# shifter.net
KiCad netlist of a schematic drawn in EAGLE
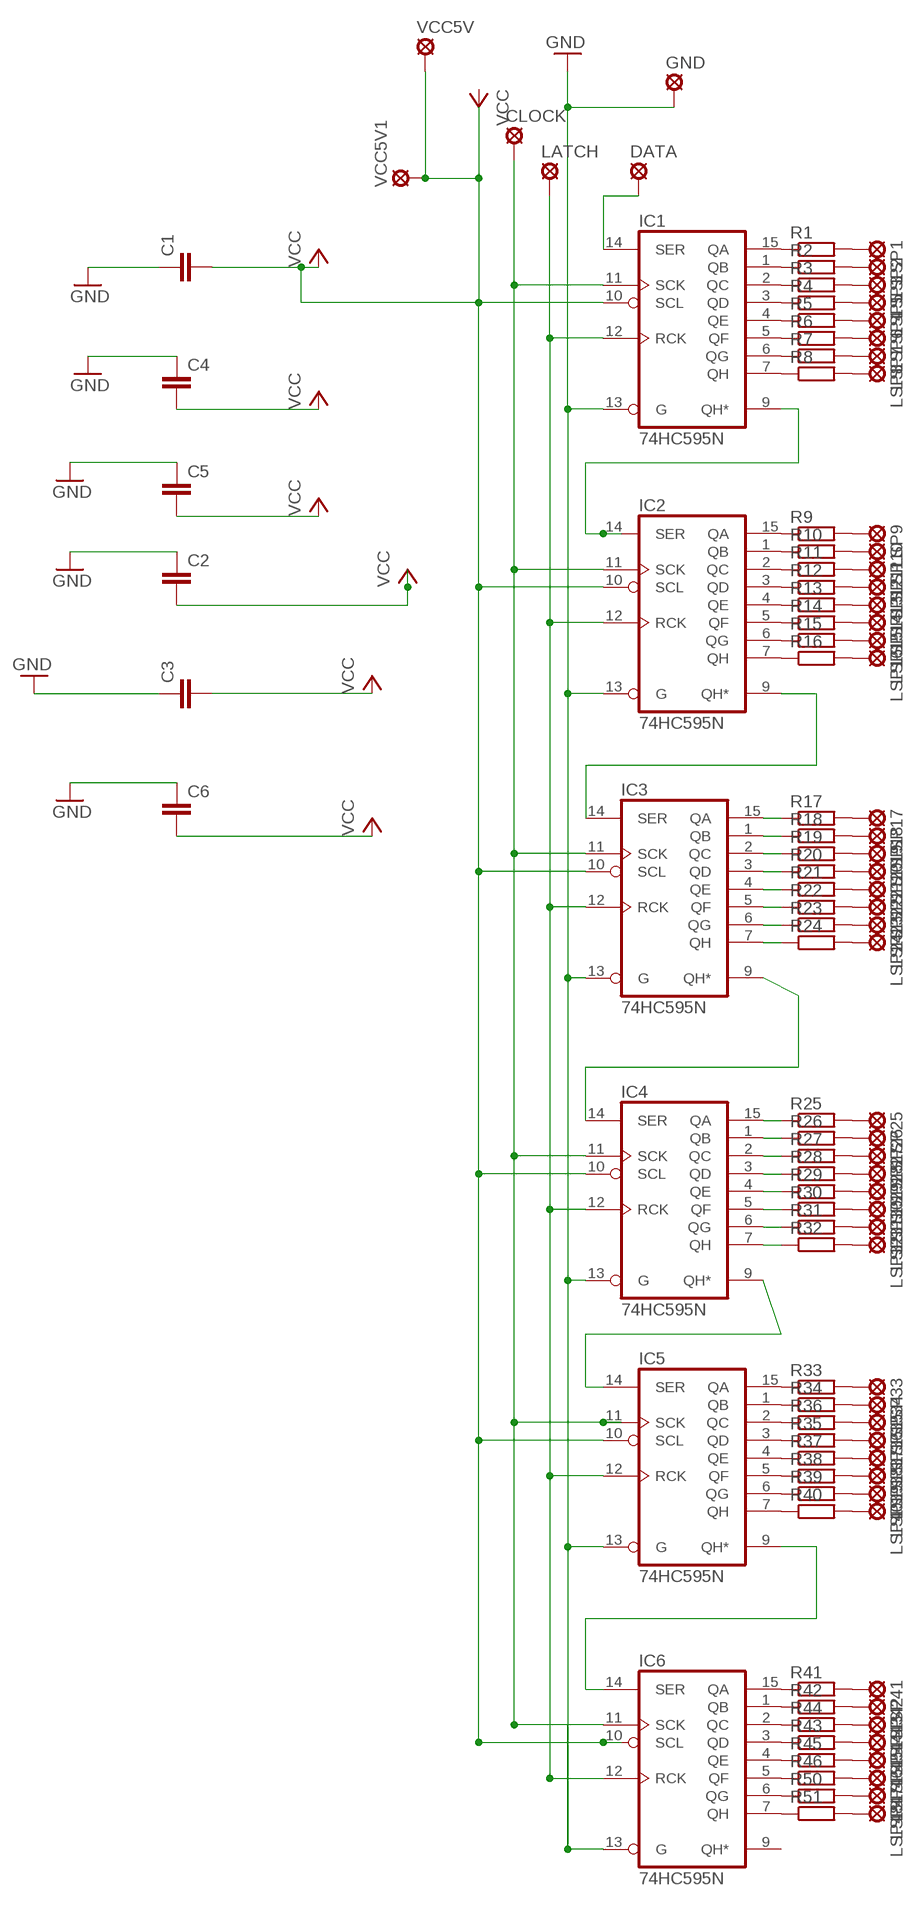
[diagram p0: schematic, sheet 1]

(export (version "E")
  (design (tool "Eeschema 10.0.6"))
  (components
    (comp (ref "C1")
      (value "C-EU025-025X050")
      (footprint "eagle-import:C025-025X050")
      (libsource (lib "eagle-import") (part "C-EU025-025X050"))
    )
    (comp (ref "C2")
      (value "C-EU025-025X050")
      (footprint "eagle-import:C025-025X050")
      (libsource (lib "eagle-import") (part "C-EU025-025X050"))
    )
    (comp (ref "C3")
      (value "C-EU025-025X050")
      (footprint "eagle-import:C025-025X050")
      (libsource (lib "eagle-import") (part "C-EU025-025X050"))
    )
    (comp (ref "C4")
      (value "C-EU025-025X050")
      (footprint "eagle-import:C025-025X050")
      (libsource (lib "eagle-import") (part "C-EU025-025X050"))
    )
    (comp (ref "C5")
      (value "C-EU025-025X050")
      (footprint "eagle-import:C025-025X050")
      (libsource (lib "eagle-import") (part "C-EU025-025X050"))
    )
    (comp (ref "C6")
      (value "C-EU025-025X050")
      (footprint "eagle-import:C025-025X050")
      (libsource (lib "eagle-import") (part "C-EU025-025X050"))
    )
    (comp (ref "CLOCK")
      (value "LSP10")
      (footprint "eagle-import:LSP10")
      (libsource (lib "eagle-import") (part "LSP10"))
    )
    (comp (ref "DATA")
      (value "LSP10")
      (footprint "eagle-import:LSP10")
      (libsource (lib "eagle-import") (part "LSP10"))
    )
    (comp (ref "GND")
      (value "LSP10")
      (footprint "eagle-import:LSP10")
      (libsource (lib "eagle-import") (part "LSP10"))
    )
    (comp (ref "IC1")
      (value "74HC595N")
      (footprint "eagle-import:DIL16")
      (libsource (lib "eagle-import") (part "74595NHC"))
    )
    (comp (ref "IC2")
      (value "74HC595N")
      (footprint "eagle-import:DIL16")
      (libsource (lib "eagle-import") (part "74595NHC"))
    )
    (comp (ref "IC3")
      (value "74HC595N")
      (footprint "eagle-import:DIL16")
      (libsource (lib "eagle-import") (part "74595NHC"))
    )
    (comp (ref "IC4")
      (value "74HC595N")
      (footprint "eagle-import:DIL16")
      (libsource (lib "eagle-import") (part "74595NHC"))
    )
    (comp (ref "IC5")
      (value "74HC595N")
      (footprint "eagle-import:DIL16")
      (libsource (lib "eagle-import") (part "74595NHC"))
    )
    (comp (ref "IC6")
      (value "74HC595N")
      (footprint "eagle-import:DIL16")
      (libsource (lib "eagle-import") (part "74595NHC"))
    )
    (comp (ref "LATCH")
      (value "LSP10")
      (footprint "eagle-import:LSP10")
      (libsource (lib "eagle-import") (part "LSP10"))
    )
    (comp (ref "LSP1")
      (value "LSP10")
      (footprint "eagle-import:LSP10")
      (libsource (lib "eagle-import") (part "LSP10"))
    )
    (comp (ref "LSP2")
      (value "LSP10")
      (footprint "eagle-import:LSP10")
      (libsource (lib "eagle-import") (part "LSP10"))
    )
    (comp (ref "LSP3")
      (value "LSP10")
      (footprint "eagle-import:LSP10")
      (libsource (lib "eagle-import") (part "LSP10"))
    )
    (comp (ref "LSP4")
      (value "LSP10")
      (footprint "eagle-import:LSP10")
      (libsource (lib "eagle-import") (part "LSP10"))
    )
    (comp (ref "LSP5")
      (value "LSP10")
      (footprint "eagle-import:LSP10")
      (libsource (lib "eagle-import") (part "LSP10"))
    )
    (comp (ref "LSP6")
      (value "LSP10")
      (footprint "eagle-import:LSP10")
      (libsource (lib "eagle-import") (part "LSP10"))
    )
    (comp (ref "LSP7")
      (value "LSP10")
      (footprint "eagle-import:LSP10")
      (libsource (lib "eagle-import") (part "LSP10"))
    )
    (comp (ref "LSP8")
      (value "LSP10")
      (footprint "eagle-import:LSP10")
      (libsource (lib "eagle-import") (part "LSP10"))
    )
    (comp (ref "LSP9")
      (value "LSP10")
      (footprint "eagle-import:LSP10")
      (libsource (lib "eagle-import") (part "LSP10"))
    )
    (comp (ref "LSP10")
      (value "LSP10")
      (footprint "eagle-import:LSP10")
      (libsource (lib "eagle-import") (part "LSP10"))
    )
    (comp (ref "LSP11")
      (value "LSP10")
      (footprint "eagle-import:LSP10")
      (libsource (lib "eagle-import") (part "LSP10"))
    )
    (comp (ref "LSP12")
      (value "LSP10")
      (footprint "eagle-import:LSP10")
      (libsource (lib "eagle-import") (part "LSP10"))
    )
    (comp (ref "LSP13")
      (value "LSP10")
      (footprint "eagle-import:LSP10")
      (libsource (lib "eagle-import") (part "LSP10"))
    )
    (comp (ref "LSP14")
      (value "LSP10")
      (footprint "eagle-import:LSP10")
      (libsource (lib "eagle-import") (part "LSP10"))
    )
    (comp (ref "LSP15")
      (value "LSP10")
      (footprint "eagle-import:LSP10")
      (libsource (lib "eagle-import") (part "LSP10"))
    )
    (comp (ref "LSP16")
      (value "LSP10")
      (footprint "eagle-import:LSP10")
      (libsource (lib "eagle-import") (part "LSP10"))
    )
    (comp (ref "LSP17")
      (value "LSP10")
      (footprint "eagle-import:LSP10")
      (libsource (lib "eagle-import") (part "LSP10"))
    )
    (comp (ref "LSP18")
      (value "LSP10")
      (footprint "eagle-import:LSP10")
      (libsource (lib "eagle-import") (part "LSP10"))
    )
    (comp (ref "LSP19")
      (value "LSP10")
      (footprint "eagle-import:LSP10")
      (libsource (lib "eagle-import") (part "LSP10"))
    )
    (comp (ref "LSP20")
      (value "LSP10")
      (footprint "eagle-import:LSP10")
      (libsource (lib "eagle-import") (part "LSP10"))
    )
    (comp (ref "LSP21")
      (value "LSP10")
      (footprint "eagle-import:LSP10")
      (libsource (lib "eagle-import") (part "LSP10"))
    )
    (comp (ref "LSP22")
      (value "LSP10")
      (footprint "eagle-import:LSP10")
      (libsource (lib "eagle-import") (part "LSP10"))
    )
    (comp (ref "LSP23")
      (value "LSP10")
      (footprint "eagle-import:LSP10")
      (libsource (lib "eagle-import") (part "LSP10"))
    )
    (comp (ref "LSP24")
      (value "LSP10")
      (footprint "eagle-import:LSP10")
      (libsource (lib "eagle-import") (part "LSP10"))
    )
    (comp (ref "LSP25")
      (value "LSP10")
      (footprint "eagle-import:LSP10")
      (libsource (lib "eagle-import") (part "LSP10"))
    )
    (comp (ref "LSP26")
      (value "LSP10")
      (footprint "eagle-import:LSP10")
      (libsource (lib "eagle-import") (part "LSP10"))
    )
    (comp (ref "LSP27")
      (value "LSP10")
      (footprint "eagle-import:LSP10")
      (libsource (lib "eagle-import") (part "LSP10"))
    )
    (comp (ref "LSP28")
      (value "LSP10")
      (footprint "eagle-import:LSP10")
      (libsource (lib "eagle-import") (part "LSP10"))
    )
    (comp (ref "LSP29")
      (value "LSP10")
      (footprint "eagle-import:LSP10")
      (libsource (lib "eagle-import") (part "LSP10"))
    )
    (comp (ref "LSP30")
      (value "LSP10")
      (footprint "eagle-import:LSP10")
      (libsource (lib "eagle-import") (part "LSP10"))
    )
    (comp (ref "LSP31")
      (value "LSP10")
      (footprint "eagle-import:LSP10")
      (libsource (lib "eagle-import") (part "LSP10"))
    )
    (comp (ref "LSP32")
      (value "LSP10")
      (footprint "eagle-import:LSP10")
      (libsource (lib "eagle-import") (part "LSP10"))
    )
    (comp (ref "LSP33")
      (value "LSP10")
      (footprint "eagle-import:LSP10")
      (libsource (lib "eagle-import") (part "LSP10"))
    )
    (comp (ref "LSP34")
      (value "LSP10")
      (footprint "eagle-import:LSP10")
      (libsource (lib "eagle-import") (part "LSP10"))
    )
    (comp (ref "LSP35")
      (value "LSP10")
      (footprint "eagle-import:LSP10")
      (libsource (lib "eagle-import") (part "LSP10"))
    )
    (comp (ref "LSP36")
      (value "LSP10")
      (footprint "eagle-import:LSP10")
      (libsource (lib "eagle-import") (part "LSP10"))
    )
    (comp (ref "LSP37")
      (value "LSP10")
      (footprint "eagle-import:LSP10")
      (libsource (lib "eagle-import") (part "LSP10"))
    )
    (comp (ref "LSP38")
      (value "LSP10")
      (footprint "eagle-import:LSP10")
      (libsource (lib "eagle-import") (part "LSP10"))
    )
    (comp (ref "LSP39")
      (value "LSP10")
      (footprint "eagle-import:LSP10")
      (libsource (lib "eagle-import") (part "LSP10"))
    )
    (comp (ref "LSP40")
      (value "LSP10")
      (footprint "eagle-import:LSP10")
      (libsource (lib "eagle-import") (part "LSP10"))
    )
    (comp (ref "LSP41")
      (value "LSP10")
      (footprint "eagle-import:LSP10")
      (libsource (lib "eagle-import") (part "LSP10"))
    )
    (comp (ref "LSP42")
      (value "LSP10")
      (footprint "eagle-import:LSP10")
      (libsource (lib "eagle-import") (part "LSP10"))
    )
    (comp (ref "LSP43")
      (value "LSP10")
      (footprint "eagle-import:LSP10")
      (libsource (lib "eagle-import") (part "LSP10"))
    )
    (comp (ref "LSP44")
      (value "LSP10")
      (footprint "eagle-import:LSP10")
      (libsource (lib "eagle-import") (part "LSP10"))
    )
    (comp (ref "LSP45")
      (value "LSP10")
      (footprint "eagle-import:LSP10")
      (libsource (lib "eagle-import") (part "LSP10"))
    )
    (comp (ref "LSP46")
      (value "LSP10")
      (footprint "eagle-import:LSP10")
      (libsource (lib "eagle-import") (part "LSP10"))
    )
    (comp (ref "LSP47")
      (value "LSP10")
      (footprint "eagle-import:LSP10")
      (libsource (lib "eagle-import") (part "LSP10"))
    )
    (comp (ref "LSP48")
      (value "LSP10")
      (footprint "eagle-import:LSP10")
      (libsource (lib "eagle-import") (part "LSP10"))
    )
    (comp (ref "R1")
      (value "R-EU_0204/2V")
      (footprint "eagle-import:0204V")
      (libsource (lib "eagle-import") (part "R-EU_0204/2V"))
    )
    (comp (ref "R2")
      (value "R-EU_0204/2V")
      (footprint "eagle-import:0204V")
      (libsource (lib "eagle-import") (part "R-EU_0204/2V"))
    )
    (comp (ref "R3")
      (value "R-EU_0204/2V")
      (footprint "eagle-import:0204V")
      (libsource (lib "eagle-import") (part "R-EU_0204/2V"))
    )
    (comp (ref "R4")
      (value "R-EU_0204/2V")
      (footprint "eagle-import:0204V")
      (libsource (lib "eagle-import") (part "R-EU_0204/2V"))
    )
    (comp (ref "R5")
      (value "R-EU_0204/2V")
      (footprint "eagle-import:0204V")
      (libsource (lib "eagle-import") (part "R-EU_0204/2V"))
    )
    (comp (ref "R6")
      (value "R-EU_0204/2V")
      (footprint "eagle-import:0204V")
      (libsource (lib "eagle-import") (part "R-EU_0204/2V"))
    )
    (comp (ref "R7")
      (value "R-EU_0204/2V")
      (footprint "eagle-import:0204V")
      (libsource (lib "eagle-import") (part "R-EU_0204/2V"))
    )
    (comp (ref "R8")
      (value "R-EU_0204/2V")
      (footprint "eagle-import:0204V")
      (libsource (lib "eagle-import") (part "R-EU_0204/2V"))
    )
    (comp (ref "R9")
      (value "R-EU_0204/2V")
      (footprint "eagle-import:0204V")
      (libsource (lib "eagle-import") (part "R-EU_0204/2V"))
    )
    (comp (ref "R10")
      (value "R-EU_0204/2V")
      (footprint "eagle-import:0204V")
      (libsource (lib "eagle-import") (part "R-EU_0204/2V"))
    )
    (comp (ref "R11")
      (value "R-EU_0204/2V")
      (footprint "eagle-import:0204V")
      (libsource (lib "eagle-import") (part "R-EU_0204/2V"))
    )
    (comp (ref "R12")
      (value "R-EU_0204/2V")
      (footprint "eagle-import:0204V")
      (libsource (lib "eagle-import") (part "R-EU_0204/2V"))
    )
    (comp (ref "R13")
      (value "R-EU_0204/2V")
      (footprint "eagle-import:0204V")
      (libsource (lib "eagle-import") (part "R-EU_0204/2V"))
    )
    (comp (ref "R14")
      (value "R-EU_0204/2V")
      (footprint "eagle-import:0204V")
      (libsource (lib "eagle-import") (part "R-EU_0204/2V"))
    )
    (comp (ref "R15")
      (value "R-EU_0204/2V")
      (footprint "eagle-import:0204V")
      (libsource (lib "eagle-import") (part "R-EU_0204/2V"))
    )
    (comp (ref "R16")
      (value "R-EU_0204/2V")
      (footprint "eagle-import:0204V")
      (libsource (lib "eagle-import") (part "R-EU_0204/2V"))
    )
    (comp (ref "R17")
      (value "R-EU_0204/2V")
      (footprint "eagle-import:0204V")
      (libsource (lib "eagle-import") (part "R-EU_0204/2V"))
    )
    (comp (ref "R18")
      (value "R-EU_0204/2V")
      (footprint "eagle-import:0204V")
      (libsource (lib "eagle-import") (part "R-EU_0204/2V"))
    )
    (comp (ref "R19")
      (value "R-EU_0204/2V")
      (footprint "eagle-import:0204V")
      (libsource (lib "eagle-import") (part "R-EU_0204/2V"))
    )
    (comp (ref "R20")
      (value "R-EU_0204/2V")
      (footprint "eagle-import:0204V")
      (libsource (lib "eagle-import") (part "R-EU_0204/2V"))
    )
    (comp (ref "R21")
      (value "R-EU_0204/2V")
      (footprint "eagle-import:0204V")
      (libsource (lib "eagle-import") (part "R-EU_0204/2V"))
    )
    (comp (ref "R22")
      (value "R-EU_0204/2V")
      (footprint "eagle-import:0204V")
      (libsource (lib "eagle-import") (part "R-EU_0204/2V"))
    )
    (comp (ref "R23")
      (value "R-EU_0204/2V")
      (footprint "eagle-import:0204V")
      (libsource (lib "eagle-import") (part "R-EU_0204/2V"))
    )
    (comp (ref "R24")
      (value "R-EU_0204/2V")
      (footprint "eagle-import:0204V")
      (libsource (lib "eagle-import") (part "R-EU_0204/2V"))
    )
    (comp (ref "R25")
      (value "R-EU_0204/2V")
      (footprint "eagle-import:0204V")
      (libsource (lib "eagle-import") (part "R-EU_0204/2V"))
    )
    (comp (ref "R26")
      (value "R-EU_0204/2V")
      (footprint "eagle-import:0204V")
      (libsource (lib "eagle-import") (part "R-EU_0204/2V"))
    )
    (comp (ref "R27")
      (value "R-EU_0204/2V")
      (footprint "eagle-import:0204V")
      (libsource (lib "eagle-import") (part "R-EU_0204/2V"))
    )
    (comp (ref "R28")
      (value "R-EU_0204/2V")
      (footprint "eagle-import:0204V")
      (libsource (lib "eagle-import") (part "R-EU_0204/2V"))
    )
    (comp (ref "R29")
      (value "R-EU_0204/2V")
      (footprint "eagle-import:0204V")
      (libsource (lib "eagle-import") (part "R-EU_0204/2V"))
    )
    (comp (ref "R30")
      (value "R-EU_0204/2V")
      (footprint "eagle-import:0204V")
      (libsource (lib "eagle-import") (part "R-EU_0204/2V"))
    )
    (comp (ref "R31")
      (value "R-EU_0204/2V")
      (footprint "eagle-import:0204V")
      (libsource (lib "eagle-import") (part "R-EU_0204/2V"))
    )
    (comp (ref "R32")
      (value "R-EU_0204/2V")
      (footprint "eagle-import:0204V")
      (libsource (lib "eagle-import") (part "R-EU_0204/2V"))
    )
    (comp (ref "R33")
      (value "R-EU_0204/2V")
      (footprint "eagle-import:0204V")
      (libsource (lib "eagle-import") (part "R-EU_0204/2V"))
    )
    (comp (ref "R34")
      (value "R-EU_0204/2V")
      (footprint "eagle-import:0204V")
      (libsource (lib "eagle-import") (part "R-EU_0204/2V"))
    )
    (comp (ref "R35")
      (value "R-EU_0204/2V")
      (footprint "eagle-import:0204V")
      (libsource (lib "eagle-import") (part "R-EU_0204/2V"))
    )
    (comp (ref "R36")
      (value "R-EU_0204/2V")
      (footprint "eagle-import:0204V")
      (libsource (lib "eagle-import") (part "R-EU_0204/2V"))
    )
    (comp (ref "R37")
      (value "R-EU_0204/2V")
      (footprint "eagle-import:0204V")
      (libsource (lib "eagle-import") (part "R-EU_0204/2V"))
    )
    (comp (ref "R38")
      (value "R-EU_0204/2V")
      (footprint "eagle-import:0204V")
      (libsource (lib "eagle-import") (part "R-EU_0204/2V"))
    )
    (comp (ref "R39")
      (value "R-EU_0204/2V")
      (footprint "eagle-import:0204V")
      (libsource (lib "eagle-import") (part "R-EU_0204/2V"))
    )
    (comp (ref "R40")
      (value "R-EU_0204/2V")
      (footprint "eagle-import:0204V")
      (libsource (lib "eagle-import") (part "R-EU_0204/2V"))
    )
    (comp (ref "R41")
      (value "R-EU_0204/2V")
      (footprint "eagle-import:0204V")
      (libsource (lib "eagle-import") (part "R-EU_0204/2V"))
    )
    (comp (ref "R42")
      (value "R-EU_0204/2V")
      (footprint "eagle-import:0204V")
      (libsource (lib "eagle-import") (part "R-EU_0204/2V"))
    )
    (comp (ref "R43")
      (value "R-EU_0204/2V")
      (footprint "eagle-import:0204V")
      (libsource (lib "eagle-import") (part "R-EU_0204/2V"))
    )
    (comp (ref "R44")
      (value "R-EU_0204/2V")
      (footprint "eagle-import:0204V")
      (libsource (lib "eagle-import") (part "R-EU_0204/2V"))
    )
    (comp (ref "R45")
      (value "R-EU_0204/2V")
      (footprint "eagle-import:0204V")
      (libsource (lib "eagle-import") (part "R-EU_0204/2V"))
    )
    (comp (ref "R46")
      (value "R-EU_0204/2V")
      (footprint "eagle-import:0204V")
      (libsource (lib "eagle-import") (part "R-EU_0204/2V"))
    )
    (comp (ref "R50")
      (value "R-EU_0204/2V")
      (footprint "eagle-import:0204V")
      (libsource (lib "eagle-import") (part "R-EU_0204/2V"))
    )
    (comp (ref "R51")
      (value "R-EU_0204/2V")
      (footprint "eagle-import:0204V")
      (libsource (lib "eagle-import") (part "R-EU_0204/2V"))
    )
    (comp (ref "VCC5V")
      (value "LSP10")
      (footprint "eagle-import:LSP10")
      (libsource (lib "eagle-import") (part "LSP10"))
    )
    (comp (ref "VCC5V1")
      (value "LSP10")
      (footprint "eagle-import:LSP10")
      (libsource (lib "eagle-import") (part "LSP10"))
    )
  )
  (nets
    (net (code "1") (name "GND") (class "Default")
      (node (ref "C1") (pin "1") (pinfunction "1_1") (pintype "passive"))
      (node (ref "C2") (pin "1") (pinfunction "1_1") (pintype "passive"))
      (node (ref "C3") (pin "1") (pinfunction "1_1") (pintype "passive"))
      (node (ref "C4") (pin "1") (pinfunction "1_1") (pintype "passive"))
      (node (ref "C5") (pin "1") (pinfunction "1_1") (pintype "passive"))
      (node (ref "C6") (pin "1") (pinfunction "1_1") (pintype "passive"))
      (node (ref "GND") (pin "MP") (pinfunction "MP_MP") (pintype "passive"))
      (node (ref "IC1") (pin "13") (pinfunction "G_13") (pintype "input"))
      (node (ref "IC2") (pin "13") (pinfunction "G_13") (pintype "input"))
      (node (ref "IC3") (pin "13") (pinfunction "G_13") (pintype "input"))
      (node (ref "IC4") (pin "13") (pinfunction "G_13") (pintype "input"))
      (node (ref "IC5") (pin "13") (pinfunction "G_13") (pintype "input"))
      (node (ref "IC6") (pin "13") (pinfunction "G_13") (pintype "input"))
    )
    (net (code "2") (name "Net-(IC1A-QA)") (class "Default")
      (node (ref "IC1") (pin "15") (pinfunction "QA_15") (pintype "tri_state"))
      (node (ref "R1") (pin "1") (pinfunction "1_1") (pintype "passive"))
    )
    (net (code "3") (name "Net-(IC1A-QB)") (class "Default")
      (node (ref "IC1") (pin "1") (pinfunction "QB_1") (pintype "tri_state"))
      (node (ref "R2") (pin "1") (pinfunction "1_1") (pintype "passive"))
    )
    (net (code "4") (name "Net-(IC1A-QC)") (class "Default")
      (node (ref "IC1") (pin "2") (pinfunction "QC_2") (pintype "tri_state"))
      (node (ref "R3") (pin "1") (pinfunction "1_1") (pintype "passive"))
    )
    (net (code "5") (name "Net-(IC1A-QD)") (class "Default")
      (node (ref "IC1") (pin "3") (pinfunction "QD_3") (pintype "tri_state"))
      (node (ref "R4") (pin "1") (pinfunction "1_1") (pintype "passive"))
    )
    (net (code "6") (name "Net-(IC1A-QE)") (class "Default")
      (node (ref "IC1") (pin "4") (pinfunction "QE_4") (pintype "tri_state"))
      (node (ref "R5") (pin "1") (pinfunction "1_1") (pintype "passive"))
    )
    (net (code "7") (name "Net-(IC1A-QF)") (class "Default")
      (node (ref "IC1") (pin "5") (pinfunction "QF_5") (pintype "tri_state"))
      (node (ref "R6") (pin "1") (pinfunction "1_1") (pintype "passive"))
    )
    (net (code "8") (name "Net-(IC1A-QG)") (class "Default")
      (node (ref "IC1") (pin "6") (pinfunction "QG_6") (pintype "tri_state"))
      (node (ref "R7") (pin "1") (pinfunction "1_1") (pintype "passive"))
    )
    (net (code "9") (name "Net-(IC1A-QH)") (class "Default")
      (node (ref "IC1") (pin "7") (pinfunction "QH_7") (pintype "tri_state"))
      (node (ref "R8") (pin "1") (pinfunction "1_1") (pintype "passive"))
    )
    (net (code "10") (name "Net-(IC1A-QH*)") (class "Default")
      (node (ref "IC1") (pin "9") (pinfunction "QH*_9") (pintype "tri_state"))
      (node (ref "IC2") (pin "14") (pinfunction "SER_14") (pintype "input"))
    )
    (net (code "11") (name "Net-(IC1A-RCK)") (class "Default")
      (node (ref "IC1") (pin "12") (pinfunction "RCK_12") (pintype "input"))
      (node (ref "IC2") (pin "12") (pinfunction "RCK_12") (pintype "input"))
      (node (ref "IC3") (pin "12") (pinfunction "RCK_12") (pintype "input"))
      (node (ref "IC4") (pin "12") (pinfunction "RCK_12") (pintype "input"))
      (node (ref "IC5") (pin "12") (pinfunction "RCK_12") (pintype "input"))
      (node (ref "IC6") (pin "12") (pinfunction "RCK_12") (pintype "input"))
      (node (ref "LATCH") (pin "MP") (pinfunction "MP_MP") (pintype "passive"))
    )
    (net (code "12") (name "Net-(IC1A-SCK)") (class "Default")
      (node (ref "CLOCK") (pin "MP") (pinfunction "MP_MP") (pintype "passive"))
      (node (ref "IC1") (pin "11") (pinfunction "SCK_11") (pintype "input"))
      (node (ref "IC2") (pin "11") (pinfunction "SCK_11") (pintype "input"))
      (node (ref "IC3") (pin "11") (pinfunction "SCK_11") (pintype "input"))
      (node (ref "IC4") (pin "11") (pinfunction "SCK_11") (pintype "input"))
      (node (ref "IC5") (pin "11") (pinfunction "SCK_11") (pintype "input"))
      (node (ref "IC6") (pin "11") (pinfunction "SCK_11") (pintype "input"))
    )
    (net (code "13") (name "Net-(IC1A-SER)") (class "Default")
      (node (ref "DATA") (pin "MP") (pinfunction "MP_MP") (pintype "passive"))
      (node (ref "IC1") (pin "14") (pinfunction "SER_14") (pintype "input"))
    )
    (net (code "14") (name "Net-(IC2A-QA)") (class "Default")
      (node (ref "IC2") (pin "15") (pinfunction "QA_15") (pintype "tri_state"))
      (node (ref "R9") (pin "1") (pinfunction "1_1") (pintype "passive"))
    )
    (net (code "15") (name "Net-(IC2A-QB)") (class "Default")
      (node (ref "IC2") (pin "1") (pinfunction "QB_1") (pintype "tri_state"))
      (node (ref "R10") (pin "1") (pinfunction "1_1") (pintype "passive"))
    )
    (net (code "16") (name "Net-(IC2A-QC)") (class "Default")
      (node (ref "IC2") (pin "2") (pinfunction "QC_2") (pintype "tri_state"))
      (node (ref "R11") (pin "1") (pinfunction "1_1") (pintype "passive"))
    )
    (net (code "17") (name "Net-(IC2A-QD)") (class "Default")
      (node (ref "IC2") (pin "3") (pinfunction "QD_3") (pintype "tri_state"))
      (node (ref "R12") (pin "1") (pinfunction "1_1") (pintype "passive"))
    )
    (net (code "18") (name "Net-(IC2A-QE)") (class "Default")
      (node (ref "IC2") (pin "4") (pinfunction "QE_4") (pintype "tri_state"))
      (node (ref "R13") (pin "1") (pinfunction "1_1") (pintype "passive"))
    )
    (net (code "19") (name "Net-(IC2A-QF)") (class "Default")
      (node (ref "IC2") (pin "5") (pinfunction "QF_5") (pintype "tri_state"))
      (node (ref "R14") (pin "1") (pinfunction "1_1") (pintype "passive"))
    )
    (net (code "20") (name "Net-(IC2A-QG)") (class "Default")
      (node (ref "IC2") (pin "6") (pinfunction "QG_6") (pintype "tri_state"))
      (node (ref "R15") (pin "1") (pinfunction "1_1") (pintype "passive"))
    )
    (net (code "21") (name "Net-(IC2A-QH)") (class "Default")
      (node (ref "IC2") (pin "7") (pinfunction "QH_7") (pintype "tri_state"))
      (node (ref "R16") (pin "1") (pinfunction "1_1") (pintype "passive"))
    )
    (net (code "22") (name "Net-(IC2A-QH*)") (class "Default")
      (node (ref "IC2") (pin "9") (pinfunction "QH*_9") (pintype "tri_state"))
      (node (ref "IC3") (pin "14") (pinfunction "SER_14") (pintype "input"))
    )
    (net (code "23") (name "Net-(IC3A-QA)") (class "Default")
      (node (ref "IC3") (pin "15") (pinfunction "QA_15") (pintype "tri_state"))
      (node (ref "R17") (pin "1") (pinfunction "1_1") (pintype "passive"))
    )
    (net (code "24") (name "Net-(IC3A-QB)") (class "Default")
      (node (ref "IC3") (pin "1") (pinfunction "QB_1") (pintype "tri_state"))
      (node (ref "R18") (pin "1") (pinfunction "1_1") (pintype "passive"))
    )
    (net (code "25") (name "Net-(IC3A-QC)") (class "Default")
      (node (ref "IC3") (pin "2") (pinfunction "QC_2") (pintype "tri_state"))
      (node (ref "R19") (pin "1") (pinfunction "1_1") (pintype "passive"))
    )
    (net (code "26") (name "Net-(IC3A-QD)") (class "Default")
      (node (ref "IC3") (pin "3") (pinfunction "QD_3") (pintype "tri_state"))
      (node (ref "R20") (pin "1") (pinfunction "1_1") (pintype "passive"))
    )
    (net (code "27") (name "Net-(IC3A-QE)") (class "Default")
      (node (ref "IC3") (pin "4") (pinfunction "QE_4") (pintype "tri_state"))
      (node (ref "R21") (pin "1") (pinfunction "1_1") (pintype "passive"))
    )
    (net (code "28") (name "Net-(IC3A-QF)") (class "Default")
      (node (ref "IC3") (pin "5") (pinfunction "QF_5") (pintype "tri_state"))
      (node (ref "R22") (pin "1") (pinfunction "1_1") (pintype "passive"))
    )
    (net (code "29") (name "Net-(IC3A-QG)") (class "Default")
      (node (ref "IC3") (pin "6") (pinfunction "QG_6") (pintype "tri_state"))
      (node (ref "R23") (pin "1") (pinfunction "1_1") (pintype "passive"))
    )
    (net (code "30") (name "Net-(IC3A-QH)") (class "Default")
      (node (ref "IC3") (pin "7") (pinfunction "QH_7") (pintype "tri_state"))
      (node (ref "R24") (pin "1") (pinfunction "1_1") (pintype "passive"))
    )
    (net (code "31") (name "Net-(IC3A-QH*)") (class "Default")
      (node (ref "IC3") (pin "9") (pinfunction "QH*_9") (pintype "tri_state"))
      (node (ref "IC4") (pin "14") (pinfunction "SER_14") (pintype "input"))
    )
    (net (code "32") (name "Net-(IC4A-QA)") (class "Default")
      (node (ref "IC4") (pin "15") (pinfunction "QA_15") (pintype "tri_state"))
      (node (ref "R25") (pin "1") (pinfunction "1_1") (pintype "passive"))
    )
    (net (code "33") (name "Net-(IC4A-QB)") (class "Default")
      (node (ref "IC4") (pin "1") (pinfunction "QB_1") (pintype "tri_state"))
      (node (ref "R26") (pin "1") (pinfunction "1_1") (pintype "passive"))
    )
    (net (code "34") (name "Net-(IC4A-QC)") (class "Default")
      (node (ref "IC4") (pin "2") (pinfunction "QC_2") (pintype "tri_state"))
      (node (ref "R27") (pin "1") (pinfunction "1_1") (pintype "passive"))
    )
    (net (code "35") (name "Net-(IC4A-QD)") (class "Default")
      (node (ref "IC4") (pin "3") (pinfunction "QD_3") (pintype "tri_state"))
      (node (ref "R28") (pin "1") (pinfunction "1_1") (pintype "passive"))
    )
    (net (code "36") (name "Net-(IC4A-QE)") (class "Default")
      (node (ref "IC4") (pin "4") (pinfunction "QE_4") (pintype "tri_state"))
      (node (ref "R29") (pin "1") (pinfunction "1_1") (pintype "passive"))
    )
    (net (code "37") (name "Net-(IC4A-QF)") (class "Default")
      (node (ref "IC4") (pin "5") (pinfunction "QF_5") (pintype "tri_state"))
      (node (ref "R30") (pin "1") (pinfunction "1_1") (pintype "passive"))
    )
    (net (code "38") (name "Net-(IC4A-QG)") (class "Default")
      (node (ref "IC4") (pin "6") (pinfunction "QG_6") (pintype "tri_state"))
      (node (ref "R31") (pin "1") (pinfunction "1_1") (pintype "passive"))
    )
    (net (code "39") (name "Net-(IC4A-QH)") (class "Default")
      (node (ref "IC4") (pin "7") (pinfunction "QH_7") (pintype "tri_state"))
      (node (ref "R32") (pin "1") (pinfunction "1_1") (pintype "passive"))
    )
    (net (code "40") (name "Net-(IC4A-QH*)") (class "Default")
      (node (ref "IC4") (pin "9") (pinfunction "QH*_9") (pintype "tri_state"))
      (node (ref "IC5") (pin "14") (pinfunction "SER_14") (pintype "input"))
    )
    (net (code "41") (name "Net-(IC5A-QA)") (class "Default")
      (node (ref "IC5") (pin "15") (pinfunction "QA_15") (pintype "tri_state"))
      (node (ref "R33") (pin "1") (pinfunction "1_1") (pintype "passive"))
    )
    (net (code "42") (name "Net-(IC5A-QB)") (class "Default")
      (node (ref "IC5") (pin "1") (pinfunction "QB_1") (pintype "tri_state"))
      (node (ref "R34") (pin "1") (pinfunction "1_1") (pintype "passive"))
    )
    (net (code "43") (name "Net-(IC5A-QC)") (class "Default")
      (node (ref "IC5") (pin "2") (pinfunction "QC_2") (pintype "tri_state"))
      (node (ref "R36") (pin "1") (pinfunction "1_1") (pintype "passive"))
    )
    (net (code "44") (name "Net-(IC5A-QD)") (class "Default")
      (node (ref "IC5") (pin "3") (pinfunction "QD_3") (pintype "tri_state"))
      (node (ref "R35") (pin "1") (pinfunction "1_1") (pintype "passive"))
    )
    (net (code "45") (name "Net-(IC5A-QE)") (class "Default")
      (node (ref "IC5") (pin "4") (pinfunction "QE_4") (pintype "tri_state"))
      (node (ref "R37") (pin "1") (pinfunction "1_1") (pintype "passive"))
    )
    (net (code "46") (name "Net-(IC5A-QF)") (class "Default")
      (node (ref "IC5") (pin "5") (pinfunction "QF_5") (pintype "tri_state"))
      (node (ref "R38") (pin "1") (pinfunction "1_1") (pintype "passive"))
    )
    (net (code "47") (name "Net-(IC5A-QG)") (class "Default")
      (node (ref "IC5") (pin "6") (pinfunction "QG_6") (pintype "tri_state"))
      (node (ref "R39") (pin "1") (pinfunction "1_1") (pintype "passive"))
    )
    (net (code "48") (name "Net-(IC5A-QH)") (class "Default")
      (node (ref "IC5") (pin "7") (pinfunction "QH_7") (pintype "tri_state"))
      (node (ref "R40") (pin "1") (pinfunction "1_1") (pintype "passive"))
    )
    (net (code "49") (name "Net-(IC5A-QH*)") (class "Default")
      (node (ref "IC5") (pin "9") (pinfunction "QH*_9") (pintype "tri_state"))
      (node (ref "IC6") (pin "14") (pinfunction "SER_14") (pintype "input"))
    )
    (net (code "50") (name "Net-(IC6A-QA)") (class "Default")
      (node (ref "IC6") (pin "15") (pinfunction "QA_15") (pintype "tri_state"))
      (node (ref "R41") (pin "1") (pinfunction "1_1") (pintype "passive"))
    )
    (net (code "51") (name "Net-(IC6A-QB)") (class "Default")
      (node (ref "IC6") (pin "1") (pinfunction "QB_1") (pintype "tri_state"))
      (node (ref "R42") (pin "1") (pinfunction "1_1") (pintype "passive"))
    )
    (net (code "52") (name "Net-(IC6A-QC)") (class "Default")
      (node (ref "IC6") (pin "2") (pinfunction "QC_2") (pintype "tri_state"))
      (node (ref "R44") (pin "1") (pinfunction "1_1") (pintype "passive"))
    )
    (net (code "53") (name "Net-(IC6A-QD)") (class "Default")
      (node (ref "IC6") (pin "3") (pinfunction "QD_3") (pintype "tri_state"))
      (node (ref "R43") (pin "1") (pinfunction "1_1") (pintype "passive"))
    )
    (net (code "54") (name "Net-(IC6A-QE)") (class "Default")
      (node (ref "IC6") (pin "4") (pinfunction "QE_4") (pintype "tri_state"))
      (node (ref "R45") (pin "1") (pinfunction "1_1") (pintype "passive"))
    )
    (net (code "55") (name "Net-(IC6A-QF)") (class "Default")
      (node (ref "IC6") (pin "5") (pinfunction "QF_5") (pintype "tri_state"))
      (node (ref "R46") (pin "1") (pinfunction "1_1") (pintype "passive"))
    )
    (net (code "56") (name "Net-(IC6A-QG)") (class "Default")
      (node (ref "IC6") (pin "6") (pinfunction "QG_6") (pintype "tri_state"))
      (node (ref "R50") (pin "1") (pinfunction "1_1") (pintype "passive"))
    )
    (net (code "57") (name "Net-(IC6A-QH)") (class "Default")
      (node (ref "IC6") (pin "7") (pinfunction "QH_7") (pintype "tri_state"))
      (node (ref "R51") (pin "1") (pinfunction "1_1") (pintype "passive"))
    )
    (net (code "58") (name "Net-(LSP1-PadMP)") (class "Default")
      (node (ref "LSP1") (pin "MP") (pinfunction "MP_MP") (pintype "passive"))
      (node (ref "R1") (pin "2") (pinfunction "2_2") (pintype "passive"))
    )
    (net (code "59") (name "Net-(LSP2-PadMP)") (class "Default")
      (node (ref "LSP2") (pin "MP") (pinfunction "MP_MP") (pintype "passive"))
      (node (ref "R2") (pin "2") (pinfunction "2_2") (pintype "passive"))
    )
    (net (code "60") (name "Net-(LSP3-PadMP)") (class "Default")
      (node (ref "LSP3") (pin "MP") (pinfunction "MP_MP") (pintype "passive"))
      (node (ref "R3") (pin "2") (pinfunction "2_2") (pintype "passive"))
    )
    (net (code "61") (name "Net-(LSP4-PadMP)") (class "Default")
      (node (ref "LSP4") (pin "MP") (pinfunction "MP_MP") (pintype "passive"))
      (node (ref "R5") (pin "2") (pinfunction "2_2") (pintype "passive"))
    )
    (net (code "62") (name "Net-(LSP5-PadMP)") (class "Default")
      (node (ref "LSP5") (pin "MP") (pinfunction "MP_MP") (pintype "passive"))
      (node (ref "R4") (pin "2") (pinfunction "2_2") (pintype "passive"))
    )
    (net (code "63") (name "Net-(LSP6-PadMP)") (class "Default")
      (node (ref "LSP6") (pin "MP") (pinfunction "MP_MP") (pintype "passive"))
      (node (ref "R6") (pin "2") (pinfunction "2_2") (pintype "passive"))
    )
    (net (code "64") (name "Net-(LSP7-PadMP)") (class "Default")
      (node (ref "LSP7") (pin "MP") (pinfunction "MP_MP") (pintype "passive"))
      (node (ref "R7") (pin "2") (pinfunction "2_2") (pintype "passive"))
    )
    (net (code "65") (name "Net-(LSP8-PadMP)") (class "Default")
      (node (ref "LSP8") (pin "MP") (pinfunction "MP_MP") (pintype "passive"))
      (node (ref "R8") (pin "2") (pinfunction "2_2") (pintype "passive"))
    )
    (net (code "66") (name "Net-(LSP9-PadMP)") (class "Default")
      (node (ref "LSP9") (pin "MP") (pinfunction "MP_MP") (pintype "passive"))
      (node (ref "R9") (pin "2") (pinfunction "2_2") (pintype "passive"))
    )
    (net (code "67") (name "Net-(LSP10-PadMP)") (class "Default")
      (node (ref "LSP10") (pin "MP") (pinfunction "MP_MP") (pintype "passive"))
      (node (ref "R10") (pin "2") (pinfunction "2_2") (pintype "passive"))
    )
    (net (code "68") (name "Net-(LSP11-PadMP)") (class "Default")
      (node (ref "LSP11") (pin "MP") (pinfunction "MP_MP") (pintype "passive"))
      (node (ref "R11") (pin "2") (pinfunction "2_2") (pintype "passive"))
    )
    (net (code "69") (name "Net-(LSP12-PadMP)") (class "Default")
      (node (ref "LSP12") (pin "MP") (pinfunction "MP_MP") (pintype "passive"))
      (node (ref "R12") (pin "2") (pinfunction "2_2") (pintype "passive"))
    )
    (net (code "70") (name "Net-(LSP13-PadMP)") (class "Default")
      (node (ref "LSP13") (pin "MP") (pinfunction "MP_MP") (pintype "passive"))
      (node (ref "R13") (pin "2") (pinfunction "2_2") (pintype "passive"))
    )
    (net (code "71") (name "Net-(LSP14-PadMP)") (class "Default")
      (node (ref "LSP14") (pin "MP") (pinfunction "MP_MP") (pintype "passive"))
      (node (ref "R14") (pin "2") (pinfunction "2_2") (pintype "passive"))
    )
    (net (code "72") (name "Net-(LSP15-PadMP)") (class "Default")
      (node (ref "LSP15") (pin "MP") (pinfunction "MP_MP") (pintype "passive"))
      (node (ref "R15") (pin "2") (pinfunction "2_2") (pintype "passive"))
    )
    (net (code "73") (name "Net-(LSP16-PadMP)") (class "Default")
      (node (ref "LSP16") (pin "MP") (pinfunction "MP_MP") (pintype "passive"))
      (node (ref "R16") (pin "2") (pinfunction "2_2") (pintype "passive"))
    )
    (net (code "74") (name "Net-(LSP17-PadMP)") (class "Default")
      (node (ref "LSP17") (pin "MP") (pinfunction "MP_MP") (pintype "passive"))
      (node (ref "R17") (pin "2") (pinfunction "2_2") (pintype "passive"))
    )
    (net (code "75") (name "Net-(LSP18-PadMP)") (class "Default")
      (node (ref "LSP18") (pin "MP") (pinfunction "MP_MP") (pintype "passive"))
      (node (ref "R18") (pin "2") (pinfunction "2_2") (pintype "passive"))
    )
    (net (code "76") (name "Net-(LSP19-PadMP)") (class "Default")
      (node (ref "LSP19") (pin "MP") (pinfunction "MP_MP") (pintype "passive"))
      (node (ref "R19") (pin "2") (pinfunction "2_2") (pintype "passive"))
    )
    (net (code "77") (name "Net-(LSP20-PadMP)") (class "Default")
      (node (ref "LSP20") (pin "MP") (pinfunction "MP_MP") (pintype "passive"))
      (node (ref "R20") (pin "2") (pinfunction "2_2") (pintype "passive"))
    )
    (net (code "78") (name "Net-(LSP21-PadMP)") (class "Default")
      (node (ref "LSP21") (pin "MP") (pinfunction "MP_MP") (pintype "passive"))
      (node (ref "R21") (pin "2") (pinfunction "2_2") (pintype "passive"))
    )
    (net (code "79") (name "Net-(LSP22-PadMP)") (class "Default")
      (node (ref "LSP22") (pin "MP") (pinfunction "MP_MP") (pintype "passive"))
      (node (ref "R22") (pin "2") (pinfunction "2_2") (pintype "passive"))
    )
    (net (code "80") (name "Net-(LSP23-PadMP)") (class "Default")
      (node (ref "LSP23") (pin "MP") (pinfunction "MP_MP") (pintype "passive"))
      (node (ref "R23") (pin "2") (pinfunction "2_2") (pintype "passive"))
    )
    (net (code "81") (name "Net-(LSP24-PadMP)") (class "Default")
      (node (ref "LSP24") (pin "MP") (pinfunction "MP_MP") (pintype "passive"))
      (node (ref "R24") (pin "2") (pinfunction "2_2") (pintype "passive"))
    )
    (net (code "82") (name "Net-(LSP25-PadMP)") (class "Default")
      (node (ref "LSP25") (pin "MP") (pinfunction "MP_MP") (pintype "passive"))
      (node (ref "R25") (pin "2") (pinfunction "2_2") (pintype "passive"))
    )
    (net (code "83") (name "Net-(LSP26-PadMP)") (class "Default")
      (node (ref "LSP26") (pin "MP") (pinfunction "MP_MP") (pintype "passive"))
      (node (ref "R26") (pin "2") (pinfunction "2_2") (pintype "passive"))
    )
    (net (code "84") (name "Net-(LSP27-PadMP)") (class "Default")
      (node (ref "LSP27") (pin "MP") (pinfunction "MP_MP") (pintype "passive"))
      (node (ref "R27") (pin "2") (pinfunction "2_2") (pintype "passive"))
    )
    (net (code "85") (name "Net-(LSP28-PadMP)") (class "Default")
      (node (ref "LSP28") (pin "MP") (pinfunction "MP_MP") (pintype "passive"))
      (node (ref "R28") (pin "2") (pinfunction "2_2") (pintype "passive"))
    )
    (net (code "86") (name "Net-(LSP29-PadMP)") (class "Default")
      (node (ref "LSP29") (pin "MP") (pinfunction "MP_MP") (pintype "passive"))
      (node (ref "R29") (pin "2") (pinfunction "2_2") (pintype "passive"))
    )
    (net (code "87") (name "Net-(LSP30-PadMP)") (class "Default")
      (node (ref "LSP30") (pin "MP") (pinfunction "MP_MP") (pintype "passive"))
      (node (ref "R30") (pin "2") (pinfunction "2_2") (pintype "passive"))
    )
    (net (code "88") (name "Net-(LSP31-PadMP)") (class "Default")
      (node (ref "LSP31") (pin "MP") (pinfunction "MP_MP") (pintype "passive"))
      (node (ref "R31") (pin "2") (pinfunction "2_2") (pintype "passive"))
    )
    (net (code "89") (name "Net-(LSP32-PadMP)") (class "Default")
      (node (ref "LSP32") (pin "MP") (pinfunction "MP_MP") (pintype "passive"))
      (node (ref "R32") (pin "2") (pinfunction "2_2") (pintype "passive"))
    )
    (net (code "90") (name "Net-(LSP33-PadMP)") (class "Default")
      (node (ref "LSP33") (pin "MP") (pinfunction "MP_MP") (pintype "passive"))
      (node (ref "R33") (pin "2") (pinfunction "2_2") (pintype "passive"))
    )
    (net (code "91") (name "Net-(LSP34-PadMP)") (class "Default")
      (node (ref "LSP34") (pin "MP") (pinfunction "MP_MP") (pintype "passive"))
      (node (ref "R34") (pin "2") (pinfunction "2_2") (pintype "passive"))
    )
    (net (code "92") (name "Net-(LSP35-PadMP)") (class "Default")
      (node (ref "LSP35") (pin "MP") (pinfunction "MP_MP") (pintype "passive"))
      (node (ref "R36") (pin "2") (pinfunction "2_2") (pintype "passive"))
    )
    (net (code "93") (name "Net-(LSP36-PadMP)") (class "Default")
      (node (ref "LSP36") (pin "MP") (pinfunction "MP_MP") (pintype "passive"))
      (node (ref "R35") (pin "2") (pinfunction "2_2") (pintype "passive"))
    )
    (net (code "94") (name "Net-(LSP37-PadMP)") (class "Default")
      (node (ref "LSP37") (pin "MP") (pinfunction "MP_MP") (pintype "passive"))
      (node (ref "R37") (pin "2") (pinfunction "2_2") (pintype "passive"))
    )
    (net (code "95") (name "Net-(LSP38-PadMP)") (class "Default")
      (node (ref "LSP38") (pin "MP") (pinfunction "MP_MP") (pintype "passive"))
      (node (ref "R38") (pin "2") (pinfunction "2_2") (pintype "passive"))
    )
    (net (code "96") (name "Net-(LSP39-PadMP)") (class "Default")
      (node (ref "LSP39") (pin "MP") (pinfunction "MP_MP") (pintype "passive"))
      (node (ref "R39") (pin "2") (pinfunction "2_2") (pintype "passive"))
    )
    (net (code "97") (name "Net-(LSP40-PadMP)") (class "Default")
      (node (ref "LSP40") (pin "MP") (pinfunction "MP_MP") (pintype "passive"))
      (node (ref "R40") (pin "2") (pinfunction "2_2") (pintype "passive"))
    )
    (net (code "98") (name "Net-(LSP41-PadMP)") (class "Default")
      (node (ref "LSP41") (pin "MP") (pinfunction "MP_MP") (pintype "passive"))
      (node (ref "R41") (pin "2") (pinfunction "2_2") (pintype "passive"))
    )
    (net (code "99") (name "Net-(LSP42-PadMP)") (class "Default")
      (node (ref "LSP42") (pin "MP") (pinfunction "MP_MP") (pintype "passive"))
      (node (ref "R42") (pin "2") (pinfunction "2_2") (pintype "passive"))
    )
    (net (code "100") (name "Net-(LSP43-PadMP)") (class "Default")
      (node (ref "LSP43") (pin "MP") (pinfunction "MP_MP") (pintype "passive"))
      (node (ref "R44") (pin "2") (pinfunction "2_2") (pintype "passive"))
    )
    (net (code "101") (name "Net-(LSP44-PadMP)") (class "Default")
      (node (ref "LSP44") (pin "MP") (pinfunction "MP_MP") (pintype "passive"))
      (node (ref "R43") (pin "2") (pinfunction "2_2") (pintype "passive"))
    )
    (net (code "102") (name "Net-(LSP45-PadMP)") (class "Default")
      (node (ref "LSP45") (pin "MP") (pinfunction "MP_MP") (pintype "passive"))
      (node (ref "R45") (pin "2") (pinfunction "2_2") (pintype "passive"))
    )
    (net (code "103") (name "Net-(LSP46-PadMP)") (class "Default")
      (node (ref "LSP46") (pin "MP") (pinfunction "MP_MP") (pintype "passive"))
      (node (ref "R46") (pin "2") (pinfunction "2_2") (pintype "passive"))
    )
    (net (code "104") (name "Net-(LSP47-PadMP)") (class "Default")
      (node (ref "LSP47") (pin "MP") (pinfunction "MP_MP") (pintype "passive"))
      (node (ref "R50") (pin "2") (pinfunction "2_2") (pintype "passive"))
    )
    (net (code "105") (name "Net-(LSP48-PadMP)") (class "Default")
      (node (ref "LSP48") (pin "MP") (pinfunction "MP_MP") (pintype "passive"))
      (node (ref "R51") (pin "2") (pinfunction "2_2") (pintype "passive"))
    )
    (net (code "106") (name "VCC") (class "Default")
      (node (ref "C1") (pin "2") (pinfunction "2_2") (pintype "passive"))
      (node (ref "C2") (pin "2") (pinfunction "2_2") (pintype "passive"))
      (node (ref "C3") (pin "2") (pinfunction "2_2") (pintype "passive"))
      (node (ref "C4") (pin "2") (pinfunction "2_2") (pintype "passive"))
      (node (ref "C5") (pin "2") (pinfunction "2_2") (pintype "passive"))
      (node (ref "C6") (pin "2") (pinfunction "2_2") (pintype "passive"))
      (node (ref "IC1") (pin "10") (pinfunction "SCL_10") (pintype "input"))
      (node (ref "IC2") (pin "10") (pinfunction "SCL_10") (pintype "input"))
      (node (ref "IC3") (pin "10") (pinfunction "SCL_10") (pintype "input"))
      (node (ref "IC4") (pin "10") (pinfunction "SCL_10") (pintype "input"))
      (node (ref "IC5") (pin "10") (pinfunction "SCL_10") (pintype "input"))
      (node (ref "IC6") (pin "10") (pinfunction "SCL_10") (pintype "input"))
      (node (ref "VCC5V") (pin "MP") (pinfunction "MP_MP") (pintype "passive"))
      (node (ref "VCC5V1") (pin "MP") (pinfunction "MP_MP") (pintype "passive"))
    )
    (net (code "107") (name "unconnected-(IC6A-QH*-Pad9)") (class "Default")
      (node (ref "IC6") (pin "9") (pinfunction "QH*_9") (pintype "tri_state"))
    )
  )
)
